# Sheet6.net
KiCad netlist of a schematic drawn in Altium Designer
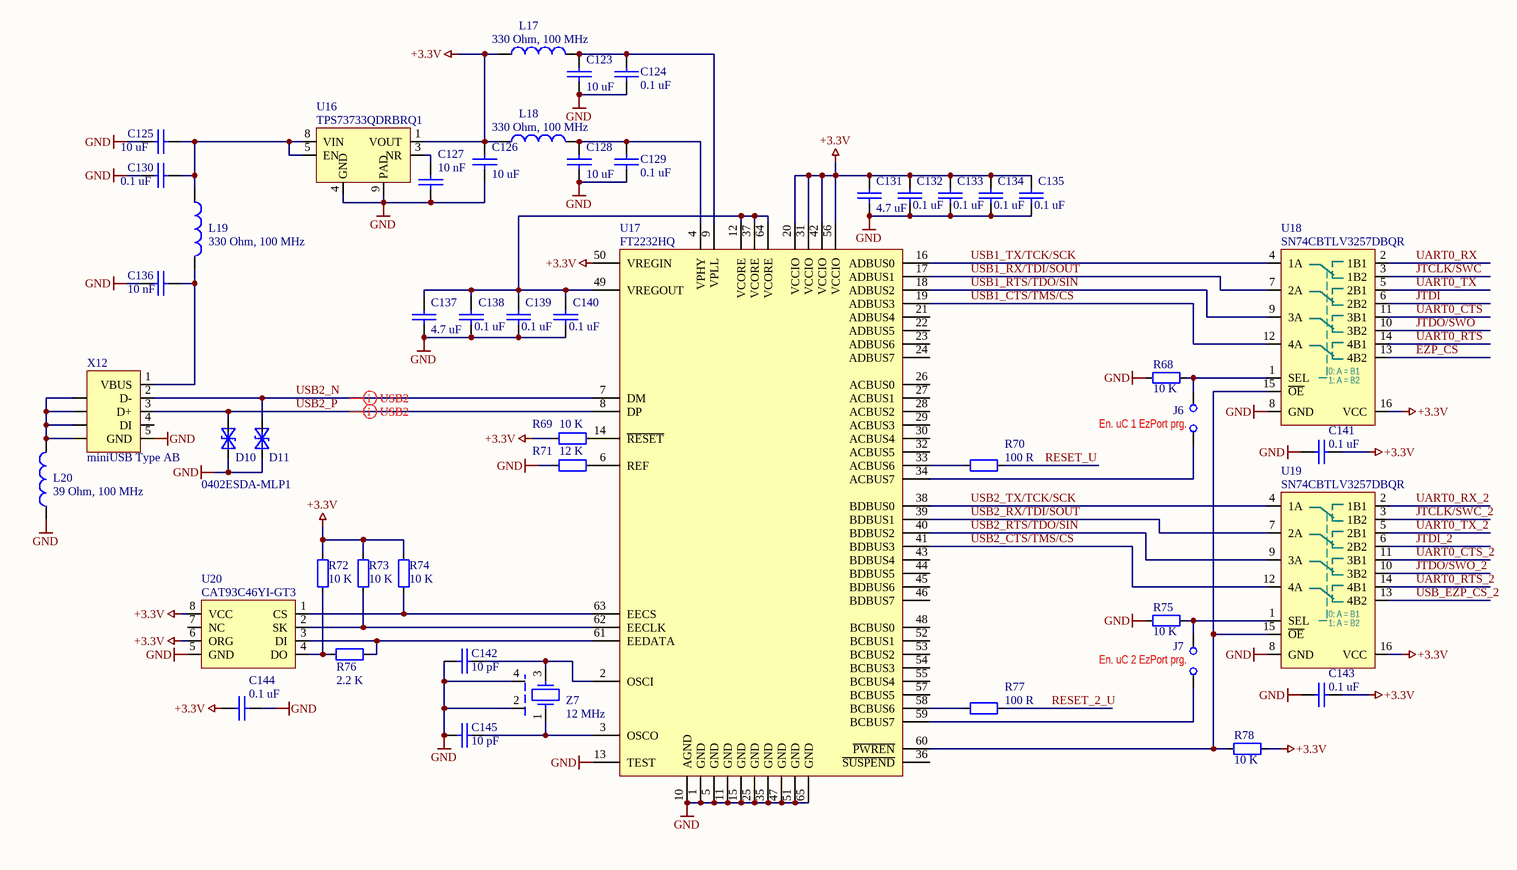
[diagram p0: Sheet6.SchDoc]

(export (version "E")
  (design (tool "Eeschema 10.0.6"))
  (components
    (comp (ref "C123")
      (value "10 uF")
      (footprint "2012[0805]")
      (description "10 uF, 16V, X5R, ±10%, 0805")
      (fields (field (name "MANUFACTURER") "TDK Corporation") (field (name "TOLERANCE") "±10%"))
      (libsource (lib "ea_Capacitors") (part "C2012X5R1C106K/0.85"))
    )
    (comp (ref "C124")
      (value "0.1 uF")
      (footprint "1005[0402]")
      (description "0.1 uF, 16V, 10%, X7R, 0402")
      (fields (field (name "TOLERANCE") "10%") (field (name "MANUFACTURER") "Murata"))
      (libsource (lib "ea_Capacitors") (part "GRM155R71C104KA88D"))
    )
    (comp (ref "C125")
      (value "10 uF")
      (footprint "2012[0805]")
      (description "10 uF, 16V, X5R, ±10%, 0805")
      (fields (field (name "MANUFACTURER") "TDK Corporation") (field (name "TOLERANCE") "±10%"))
      (libsource (lib "ea_Capacitors") (part "C2012X5R1C106K/0.85"))
    )
    (comp (ref "C126")
      (value "10 uF")
      (footprint "2012[0805]")
      (description "10 uF, 16V, X5R, ±10%, 0805")
      (fields (field (name "MANUFACTURER") "TDK Corporation") (field (name "TOLERANCE") "±10%"))
      (libsource (lib "ea_Capacitors") (part "C2012X5R1C106K/0.85"))
    )
    (comp (ref "C127")
      (value "10 nF")
      (footprint "1005[0402]")
      (description "10 nF, 16V, 10%, X7R, 0402")
      (fields (field (name "TOLERANCE") "10%") (field (name "MANUFACTURER") "SAMSUNG"))
      (libsource (lib "ea_Capacitors") (part "GRM155R71C103KA01D_1"))
    )
    (comp (ref "C128")
      (value "10 uF")
      (footprint "2012[0805]")
      (description "10 uF, 16V, X5R, ±10%, 0805")
      (fields (field (name "MANUFACTURER") "TDK Corporation") (field (name "TOLERANCE") "±10%"))
      (libsource (lib "ea_Capacitors") (part "C2012X5R1C106K/0.85"))
    )
    (comp (ref "C129")
      (value "0.1 uF")
      (footprint "1005[0402]")
      (description "0.1 uF, 16V, 10%, X7R, 0402")
      (fields (field (name "TOLERANCE") "10%") (field (name "MANUFACTURER") "Murata"))
      (libsource (lib "ea_Capacitors") (part "GRM155R71C104KA88D"))
    )
    (comp (ref "C130")
      (value "0.1 uF")
      (footprint "1608[0603]")
      (description "0.1 uF, 25V, 10% , X7R,  0603 SMD MLC Capacitor")
      (fields (field (name "TOLERANCE") "10%") (field (name "MANUFACTURER") "SAMSUNG"))
      (libsource (lib "ea_Capacitors") (part "CVNF100K0603-25"))
    )
    (comp (ref "C131")
      (value "4.7 uF")
      (footprint "1608[0603]")
      (description "4.7 uF, 10V, 10%, X5R, 0603")
      (fields (field (name "TOLERANCE") "+-10%") (field (name "MANUFACTURER") "Taiyo Yuden"))
      (libsource (lib "ea_Capacitors") (part "LMK107BJ475KA-T"))
    )
    (comp (ref "C132")
      (value "0.1 uF")
      (footprint "1005[0402]")
      (description "0.1 uF, 16V, 10%, X7R, 0402")
      (fields (field (name "TOLERANCE") "10%") (field (name "MANUFACTURER") "Murata"))
      (libsource (lib "ea_Capacitors") (part "GRM155R71C104KA88D"))
    )
    (comp (ref "C133")
      (value "0.1 uF")
      (footprint "1005[0402]")
      (description "0.1 uF, 16V, 10%, X7R, 0402")
      (fields (field (name "TOLERANCE") "10%") (field (name "MANUFACTURER") "Murata"))
      (libsource (lib "ea_Capacitors") (part "GRM155R71C104KA88D"))
    )
    (comp (ref "C134")
      (value "0.1 uF")
      (footprint "1005[0402]")
      (description "0.1 uF, 16V, 10%, X7R, 0402")
      (fields (field (name "TOLERANCE") "10%") (field (name "MANUFACTURER") "Murata"))
      (libsource (lib "ea_Capacitors") (part "GRM155R71C104KA88D"))
    )
    (comp (ref "C135")
      (value "0.1 uF")
      (footprint "1005[0402]")
      (description "0.1 uF, 16V, 10%, X7R, 0402")
      (fields (field (name "TOLERANCE") "10%") (field (name "MANUFACTURER") "Murata"))
      (libsource (lib "ea_Capacitors") (part "GRM155R71C104KA88D"))
    )
    (comp (ref "C136")
      (value "10 nF")
      (footprint "1608[0603]")
      (description "10 nF, 50V, 5%, X7R, 0603 SMD MLC Capacitor")
      (fields (field (name "TOLERANCE") "5%") (field (name "MANUFACTURER") "SAMSUNG"))
      (libsource (lib "ea_Capacitors") (part "CVNF010K0603"))
    )
    (comp (ref "C137")
      (value "4.7 uF")
      (footprint "1608[0603]")
      (description "4.7 uF, 10V, 10%, X5R, 0603")
      (fields (field (name "TOLERANCE") "+-10%") (field (name "MANUFACTURER") "Taiyo Yuden"))
      (libsource (lib "ea_Capacitors") (part "LMK107BJ475KA-T"))
    )
    (comp (ref "C138")
      (value "0.1 uF")
      (footprint "1005[0402]")
      (description "0.1 uF, 16V, 10%, X7R, 0402")
      (fields (field (name "TOLERANCE") "10%") (field (name "MANUFACTURER") "Murata"))
      (libsource (lib "ea_Capacitors") (part "GRM155R71C104KA88D"))
    )
    (comp (ref "C139")
      (value "0.1 uF")
      (footprint "1005[0402]")
      (description "0.1 uF, 16V, 10%, X7R, 0402")
      (fields (field (name "TOLERANCE") "10%") (field (name "MANUFACTURER") "Murata"))
      (libsource (lib "ea_Capacitors") (part "GRM155R71C104KA88D"))
    )
    (comp (ref "C140")
      (value "0.1 uF")
      (footprint "1005[0402]")
      (description "0.1 uF, 16V, 10%, X7R, 0402")
      (fields (field (name "TOLERANCE") "10%") (field (name "MANUFACTURER") "Murata"))
      (libsource (lib "ea_Capacitors") (part "GRM155R71C104KA88D"))
    )
    (comp (ref "C141")
      (value "0.1 uF")
      (footprint "1005[0402]")
      (description "0.1 uF, 16V, 10%, X7R, 0402")
      (fields (field (name "TOLERANCE") "10%") (field (name "MANUFACTURER") "Murata"))
      (libsource (lib "ea_Capacitors") (part "GRM155R71C104KA88D"))
    )
    (comp (ref "C142")
      (value "10 pF")
      (footprint "1608[0603]")
      (description "10 pF, 50V, 5%, NP0, 0603 SMD MLC Capacitor")
      (fields (field (name "MANUFACTURER") "Kemet") (field (name "TOLERANCE") "5%"))
      (libsource (lib "ea_Capacitors") (part "CCPF010K0603"))
    )
    (comp (ref "C143")
      (value "0.1 uF")
      (footprint "1005[0402]")
      (description "0.1 uF, 16V, 10%, X7R, 0402")
      (fields (field (name "TOLERANCE") "10%") (field (name "MANUFACTURER") "Murata"))
      (libsource (lib "ea_Capacitors") (part "GRM155R71C104KA88D"))
    )
    (comp (ref "C144")
      (value "0.1 uF")
      (footprint "1005[0402]")
      (description "0.1 uF, 16V, 10%, X7R, 0402")
      (fields (field (name "TOLERANCE") "10%") (field (name "MANUFACTURER") "Murata"))
      (libsource (lib "ea_Capacitors") (part "GRM155R71C104KA88D"))
    )
    (comp (ref "C145")
      (value "10 pF")
      (footprint "1608[0603]")
      (description "10 pF, 50V, 5%, NP0, 0603 SMD MLC Capacitor")
      (fields (field (name "MANUFACTURER") "Kemet") (field (name "TOLERANCE") "5%"))
      (libsource (lib "ea_Capacitors") (part "CCPF010K0603"))
    )
    (comp (ref "D10")
      (value "0402ESDA-MLP1")
      (footprint "0402")
      (description "SUPPRESSOR ESD 30VDC 0402 HFREE")
      (fields (field (name "MANUFACTURER") "Cooper Bussmann") (field (name "PARTNUM") "283-2964-2-ND"))
      (libsource (lib "ea_TVS_protection") (part "0402ESDA-MLP1"))
    )
    (comp (ref "D11")
      (value "0402ESDA-MLP1")
      (footprint "0402")
      (description "SUPPRESSOR ESD 30VDC 0402 HFREE")
      (fields (field (name "MANUFACTURER") "Cooper Bussmann") (field (name "PARTNUM") "283-2964-2-ND"))
      (libsource (lib "ea_TVS_protection") (part "0402ESDA-MLP1"))
    )
    (comp (ref "J6")
      (value "PH1-02-TA-HT")
      (footprint "HDR1X2V")
      (description "2 Pos. 2.54 mm Single Row Through Hole Straight Pin Header")
      (fields (field (name "MANUFACTURER") "ADAM TECH"))
      (libsource (lib "ea_Commutation") (part "Jumper"))
    )
    (comp (ref "J7")
      (value "PH1-02-TA-HT")
      (footprint "HDR1X2V")
      (description "2 Pos. 2.54 mm Single Row Through Hole Straight Pin Header")
      (fields (field (name "MANUFACTURER") "ADAM TECH"))
      (libsource (lib "ea_Commutation") (part "Jumper"))
    )
    (comp (ref "L17")
      (value "330 Ohm, 100 MHz")
      (footprint "0603")
      (description "Ferrite bead, 330 Ohm, 100 MHz,  1.5 A, 0.07 Ohm")
      (fields
        (field (name "MANUFACTURER") "Murata Electronics North America")
        (field (name "PARTNUM") "BLM18SG331TN1D")
      )
      (libsource (lib "*") (part "BLM18SG331TN1D"))
    )
    (comp (ref "L18")
      (value "330 Ohm, 100 MHz")
      (footprint "0603")
      (description "Ferrite bead, 330 Ohm, 100 MHz,  1.5 A, 0.07 Ohm")
      (fields
        (field (name "MANUFACTURER") "Murata Electronics North America")
        (field (name "PARTNUM") "BLM18SG331TN1D")
      )
      (libsource (lib "*") (part "BLM18SG331TN1D"))
    )
    (comp (ref "L19")
      (value "330 Ohm, 100 MHz")
      (footprint "0603")
      (description "Ferrite bead, 330 Ohm, 100 MHz,  1.5 A, 0.07 Ohm")
      (fields
        (field (name "MANUFACTURER") "Murata Electronics North America")
        (field (name "PARTNUM") "BLM18SG331TN1D")
      )
      (libsource (lib "*") (part "BLM18SG331TN1D"))
    )
    (comp (ref "L20")
      (value "39 Ohm, 100 MHz")
      (footprint "0805")
      (description "Ferrite bead, 39 Ohm, 100 MHz,  4 A")
      (fields (field (name "MANUFACTURER") "Panasonic - ECG") (field (name "PARTNUM") "P10191TR-ND"))
      (libsource (lib "*") (part "EXC-ML20A390U"))
    )
    (comp (ref "R68")
      (value "10 K")
      (footprint "0603")
      (description "10 K, 1%, 0603, SMD Resistor, Taped")
      (fields (field (name "MANUFACTURER") "PANASONIC") (field (name "TOLERANCE") "1%"))
      (libsource (lib "ea_Resistors") (part "RL0603K010-1"))
    )
    (comp (ref "R69")
      (value "10 K")
      (footprint "0603")
      (description "10 K, 1%, 0603, SMD Resistor, Taped")
      (fields (field (name "MANUFACTURER") "PANASONIC") (field (name "TOLERANCE") "1%"))
      (libsource (lib "") (part "RL0603K010-1_2"))
    )
    (comp (ref "R70")
      (value "100 R")
      (footprint "0603")
      (description "100 R, 1%, 0603, SMD Resistor, Taped")
      (fields (field (name "MANUFACTURER") "PANASONIC") (field (name "TOLERANCE") "1%"))
      (libsource (lib "ea_Resistors") (part "RL0603E100-1"))
    )
    (comp (ref "R71")
      (value "12 K")
      (footprint "0603")
      (description "12 K, 1%, 0603, SMD Resistor, Taped")
      (fields (field (name "MANUFACTURER") "YAGEO AMERICA CORPORATION") (field (name "TOLERANCE") "1%"))
      (libsource (lib "ea_Resistors") (part "RL0603K012-1_1"))
    )
    (comp (ref "R72")
      (value "10 K")
      (footprint "0603")
      (description "10 K, 1%, 0603, SMD Resistor, Taped")
      (fields (field (name "MANUFACTURER") "PANASONIC") (field (name "TOLERANCE") "1%"))
      (libsource (lib "") (part "RL0603K010-1_1"))
    )
    (comp (ref "R73")
      (value "10 K")
      (footprint "0603")
      (description "10 K, 1%, 0603, SMD Resistor, Taped")
      (fields (field (name "MANUFACTURER") "PANASONIC") (field (name "TOLERANCE") "1%"))
      (libsource (lib "") (part "RL0603K010-1_1"))
    )
    (comp (ref "R74")
      (value "10 K")
      (footprint "0603")
      (description "10 K, 1%, 0603, SMD Resistor, Taped")
      (fields (field (name "MANUFACTURER") "PANASONIC") (field (name "TOLERANCE") "1%"))
      (libsource (lib "") (part "RL0603K010-1_1"))
    )
    (comp (ref "R75")
      (value "10 K")
      (footprint "0603")
      (description "10 K, 1%, 0603, SMD Resistor, Taped")
      (fields (field (name "MANUFACTURER") "PANASONIC") (field (name "TOLERANCE") "1%"))
      (libsource (lib "ea_Resistors") (part "RL0603K010-1"))
    )
    (comp (ref "R76")
      (value "2.2 K")
      (footprint "0603")
      (description "2.2 K, 1%, 0603, SMD Resistor, Taped")
      (fields (field (name "MANUFACTURER") "YAGEO AMERICA CORPORATION") (field (name "TOLERANCE") "1%"))
      (libsource (lib "ea_Resistors") (part "RL0603K002.2-1_1"))
    )
    (comp (ref "R77")
      (value "100 R")
      (footprint "0603")
      (description "100 R, 1%, 0603, SMD Resistor, Taped")
      (fields (field (name "MANUFACTURER") "PANASONIC") (field (name "TOLERANCE") "1%"))
      (libsource (lib "ea_Resistors") (part "RL0603E100-1"))
    )
    (comp (ref "R78")
      (value "10 K")
      (footprint "0603")
      (description "10 K, 1%, 0603, SMD Resistor, Taped")
      (fields (field (name "MANUFACTURER") "PANASONIC") (field (name "TOLERANCE") "1%"))
      (libsource (lib "ea_Resistors") (part "RL0603K010-1"))
    )
    (comp (ref "U16")
      (value "TPS73733QDRBRQ1")
      (footprint "TI DRB (S-PVSON-N8)")
      (description "LDO 3.3V 1A , up to 5.5 V, -40..125C,  8-SON")
      (fields (field (name "MANUFACTURER") "Texas Instruments") (field (name "PARTNUM") "296-24157-1-ND"))
      (libsource (lib "ea_IC_Power_Reg_Ref_Sw") (part "TPS73733QDRBRQ1"))
    )
    (comp (ref "U17")
      (value "FT2232HQ")
      (footprint "QFN-64")
      (description "Dual High Speed USB to Multipurpose UART/FIFO")
      (fields
        (field (name "MANUFACTURER") "FTDI, Future Technology Devices International Ltd")
        (field (name "PARTNUM") "768-1024-1-ND")
      )
      (libsource (lib "ea_IC_Interfaces") (part "FT2232HQ"))
    )
    (comp (ref "U18")
      (value "SN74CBTLV3257DBQR")
      (footprint "TI DBQ 16pin (R-PDSO-G16)")
      (description "LV DUAL FET MUX/DEMUX, 2.3..3.6V,  -40..85 C, 16SSOP")
      (fields (field (name "MANUFACTURER") "Texas Instruments") (field (name "PARTNUM") "296-9135-1-ND"))
      (libsource (lib "ea_IC_Logic") (part "SN74CBTLV3257DBQR"))
    )
    (comp (ref "U19")
      (value "SN74CBTLV3257DBQR")
      (footprint "TI DBQ 16pin (R-PDSO-G16)")
      (description "LV DUAL FET MUX/DEMUX, 2.3..3.6V,  -40..85 C, 16SSOP")
      (fields (field (name "MANUFACTURER") "Texas Instruments") (field (name "PARTNUM") "296-9135-1-ND"))
      (libsource (lib "ea_IC_Logic") (part "SN74CBTLV3257DBQR"))
    )
    (comp (ref "U20")
      (value "CAT93C46YI-GT3")
      (footprint "TSSOP-8")
      (description "EEPROM 1KBIT 2MHZ 8TSSOP, -40..85 C")
      (fields
        (field (name "MANUFACTURER") "ON Semiconductor")
        (field (name "PARTNUM") "CAT93C46YI-GT3OSCT-ND")
      )
      (libsource (lib "ea_IC_NOR_NAND_FLASH") (part "CAT93C46YI-GT3"))
    )
    (comp (ref "X12")
      (value "miniUSB Type AB")
      (footprint "USB AB 56579-0576 Molex")
      (description "SMD USB - OTG, miniUSB Type AB")
      (fields
        (field (name "MANUFACTURER") "Molex/Waldom Electronics Corp")
        (field (name "PARTNUM") "WM17122CT-ND")
      )
      (libsource (lib "ea_Connectors") (part "USB AB 56579-0576"))
    )
    (comp (ref "Z7")
      (value "12 MHz")
      (footprint "DSX321G")
      (description "12 MHz, 8 pF, ±15ppm, -10...+75 С")
      (fields (field (name "MANUFACTURER") "NDK") (field (name "PARTNUM") "644-1047-1-ND"))
      (libsource (lib "ea_OSC_CLK_GEN") (part "NX3225SA-12.000MHZ-STD-CSR-1"))
    )
  )
  (nets
    (net (code "1") (name "+3.3V") (class "Default")
      (node (ref "C126") (pin "1") (pinfunction "1_1") (pintype "passive"))
      (node (ref "C131") (pin "2") (pinfunction "2_2") (pintype "passive"))
      (node (ref "C132") (pin "2") (pinfunction "2_2") (pintype "passive"))
      (node (ref "C133") (pin "2") (pinfunction "2_2") (pintype "passive"))
      (node (ref "C134") (pin "2") (pinfunction "2_2") (pintype "passive"))
      (node (ref "C135") (pin "2") (pinfunction "2_2") (pintype "passive"))
      (node (ref "C141") (pin "1") (pinfunction "1_1") (pintype "passive"))
      (node (ref "C143") (pin "1") (pinfunction "1_1") (pintype "passive"))
      (node (ref "C144") (pin "2") (pinfunction "2_2") (pintype "passive"))
      (node (ref "L17") (pin "1") (pinfunction "1_1") (pintype "passive"))
      (node (ref "L18") (pin "1") (pinfunction "1_1") (pintype "passive"))
      (node (ref "R69") (pin "2") (pinfunction "2_2") (pintype "passive"))
      (node (ref "R72") (pin "2") (pinfunction "2_2") (pintype "passive"))
      (node (ref "R73") (pin "2") (pinfunction "2_2") (pintype "passive"))
      (node (ref "R74") (pin "2") (pinfunction "2_2") (pintype "passive"))
      (node (ref "R78") (pin "2") (pinfunction "2_2") (pintype "passive"))
      (node (ref "U16") (pin "1") (pinfunction "VOUT_1") (pintype "passive"))
      (node (ref "U17") (pin "20") (pinfunction "VCCIO_20") (pintype "passive"))
      (node (ref "U17") (pin "31") (pinfunction "VCCIO_31") (pintype "passive"))
      (node (ref "U17") (pin "42") (pinfunction "VCCIO_42") (pintype "passive"))
      (node (ref "U17") (pin "50") (pinfunction "VREGIN_50") (pintype "passive"))
      (node (ref "U17") (pin "56") (pinfunction "VCCIO_56") (pintype "passive"))
      (node (ref "U18") (pin "16") (pinfunction "VCC_16") (pintype "passive"))
      (node (ref "U19") (pin "16") (pinfunction "VCC_16") (pintype "passive"))
      (node (ref "U20") (pin "6") (pinfunction "ORG_6") (pintype "passive"))
      (node (ref "U20") (pin "8") (pinfunction "VCC_8") (pintype "passive"))
    )
    (net (code "2") (name "/EZP_CS") (class "Default")
      (node (ref "U18") (pin "13") (pinfunction "4B2_13") (pintype "passive"))
    )
    (net (code "3") (name "/JTCLK{slash}SWC") (class "Default")
      (node (ref "U18") (pin "3") (pinfunction "1B2_3") (pintype "passive"))
    )
    (net (code "4") (name "/JTCLK{slash}SWC_2") (class "Default")
      (node (ref "U19") (pin "3") (pinfunction "1B2_3") (pintype "passive"))
    )
    (net (code "5") (name "/JTDI") (class "Default")
      (node (ref "U18") (pin "6") (pinfunction "2B2_6") (pintype "passive"))
    )
    (net (code "6") (name "/JTDI_2") (class "Default")
      (node (ref "U19") (pin "6") (pinfunction "2B2_6") (pintype "passive"))
    )
    (net (code "7") (name "/JTDO{slash}SWO") (class "Default")
      (node (ref "U18") (pin "10") (pinfunction "3B2_10") (pintype "passive"))
    )
    (net (code "8") (name "/JTDO{slash}SWO_2") (class "Default")
      (node (ref "U19") (pin "10") (pinfunction "3B2_10") (pintype "passive"))
    )
    (net (code "9") (name "/RESET_2_U") (class "Default")
      (node (ref "R77") (pin "1") (pinfunction "1_1") (pintype "passive"))
    )
    (net (code "10") (name "/RESET_U") (class "Default")
      (node (ref "R70") (pin "1") (pinfunction "1_1") (pintype "passive"))
    )
    (net (code "11") (name "/UART0_CTS") (class "Default")
      (node (ref "U18") (pin "11") (pinfunction "3B1_11") (pintype "passive"))
    )
    (net (code "12") (name "/UART0_CTS_2") (class "Default")
      (node (ref "U19") (pin "11") (pinfunction "3B1_11") (pintype "passive"))
    )
    (net (code "13") (name "/UART0_RTS") (class "Default")
      (node (ref "U18") (pin "14") (pinfunction "4B1_14") (pintype "passive"))
    )
    (net (code "14") (name "/UART0_RTS_2") (class "Default")
      (node (ref "U19") (pin "14") (pinfunction "4B1_14") (pintype "passive"))
    )
    (net (code "15") (name "/UART0_RX") (class "Default")
      (node (ref "U18") (pin "2") (pinfunction "1B1_2") (pintype "passive"))
    )
    (net (code "16") (name "/UART0_RX_2") (class "Default")
      (node (ref "U19") (pin "2") (pinfunction "1B1_2") (pintype "passive"))
    )
    (net (code "17") (name "/UART0_TX") (class "Default")
      (node (ref "U18") (pin "5") (pinfunction "2B1_5") (pintype "passive"))
    )
    (net (code "18") (name "/UART0_TX_2") (class "Default")
      (node (ref "U19") (pin "5") (pinfunction "2B1_5") (pintype "passive"))
    )
    (net (code "19") (name "/USB1_CTS{slash}TMS{slash}CS") (class "Default")
      (node (ref "U17") (pin "19") (pinfunction "ADBUS3_19") (pintype "passive"))
      (node (ref "U18") (pin "12") (pinfunction "4A_12") (pintype "passive"))
    )
    (net (code "20") (name "/USB1_RTS{slash}TDO{slash}SIN") (class "Default")
      (node (ref "U17") (pin "18") (pinfunction "ADBUS2_18") (pintype "passive"))
      (node (ref "U18") (pin "9") (pinfunction "3A_9") (pintype "passive"))
    )
    (net (code "21") (name "/USB1_RX{slash}TDI{slash}SOUT") (class "Default")
      (node (ref "U17") (pin "17") (pinfunction "ADBUS1_17") (pintype "passive"))
      (node (ref "U18") (pin "7") (pinfunction "2A_7") (pintype "passive"))
    )
    (net (code "22") (name "/USB1_TX{slash}TCK{slash}SCK") (class "Default")
      (node (ref "U17") (pin "16") (pinfunction "ADBUS0_16") (pintype "passive"))
      (node (ref "U18") (pin "4") (pinfunction "1A_4") (pintype "passive"))
    )
    (net (code "23") (name "/USB2_CTS{slash}TMS{slash}CS") (class "Default")
      (node (ref "U17") (pin "41") (pinfunction "BDBUS3_41") (pintype "passive"))
      (node (ref "U19") (pin "12") (pinfunction "4A_12") (pintype "passive"))
    )
    (net (code "24") (name "/USB2_N") (class "Default")
      (node (ref "D11") (pin "2") (pinfunction "A_2") (pintype "passive"))
      (node (ref "U17") (pin "7") (pinfunction "DM_7") (pintype "passive"))
      (node (ref "X12") (pin "2") (pinfunction "D-_2") (pintype "bidirectional"))
    )
    (net (code "25") (name "/USB2_P") (class "Default")
      (node (ref "D10") (pin "2") (pinfunction "A_2") (pintype "passive"))
      (node (ref "U17") (pin "8") (pinfunction "DP_8") (pintype "passive"))
      (node (ref "X12") (pin "3") (pinfunction "D+_3") (pintype "bidirectional"))
    )
    (net (code "26") (name "/USB2_RTS{slash}TDO{slash}SIN") (class "Default")
      (node (ref "U17") (pin "40") (pinfunction "BDBUS2_40") (pintype "passive"))
      (node (ref "U19") (pin "9") (pinfunction "3A_9") (pintype "passive"))
    )
    (net (code "27") (name "/USB2_RX{slash}TDI{slash}SOUT") (class "Default")
      (node (ref "U17") (pin "39") (pinfunction "BDBUS1_39") (pintype "passive"))
      (node (ref "U19") (pin "7") (pinfunction "2A_7") (pintype "passive"))
    )
    (net (code "28") (name "/USB2_TX{slash}TCK{slash}SCK") (class "Default")
      (node (ref "U17") (pin "38") (pinfunction "BDBUS0_38") (pintype "passive"))
      (node (ref "U19") (pin "4") (pinfunction "1A_4") (pintype "passive"))
    )
    (net (code "29") (name "/USB_EZP_CS_2") (class "Default")
      (node (ref "U19") (pin "13") (pinfunction "4B2_13") (pintype "passive"))
    )
    (net (code "30") (name "GND") (class "Default")
      (node (ref "C123") (pin "2") (pinfunction "2_2") (pintype "passive"))
      (node (ref "C124") (pin "1") (pinfunction "1_1") (pintype "passive"))
      (node (ref "C125") (pin "1") (pinfunction "1_1") (pintype "passive"))
      (node (ref "C126") (pin "2") (pinfunction "2_2") (pintype "passive"))
      (node (ref "C127") (pin "2") (pinfunction "2_2") (pintype "passive"))
      (node (ref "C128") (pin "2") (pinfunction "2_2") (pintype "passive"))
      (node (ref "C129") (pin "1") (pinfunction "1_1") (pintype "passive"))
      (node (ref "C130") (pin "2") (pinfunction "2_2") (pintype "passive"))
      (node (ref "C131") (pin "1") (pinfunction "1_1") (pintype "passive"))
      (node (ref "C132") (pin "1") (pinfunction "1_1") (pintype "passive"))
      (node (ref "C133") (pin "1") (pinfunction "1_1") (pintype "passive"))
      (node (ref "C134") (pin "1") (pinfunction "1_1") (pintype "passive"))
      (node (ref "C135") (pin "1") (pinfunction "1_1") (pintype "passive"))
      (node (ref "C136") (pin "2") (pinfunction "2_2") (pintype "passive"))
      (node (ref "C137") (pin "1") (pinfunction "1_1") (pintype "passive"))
      (node (ref "C138") (pin "1") (pinfunction "1_1") (pintype "passive"))
      (node (ref "C139") (pin "1") (pinfunction "1_1") (pintype "passive"))
      (node (ref "C140") (pin "1") (pinfunction "1_1") (pintype "passive"))
      (node (ref "C141") (pin "2") (pinfunction "2_2") (pintype "passive"))
      (node (ref "C142") (pin "2") (pinfunction "2_2") (pintype "passive"))
      (node (ref "C143") (pin "2") (pinfunction "2_2") (pintype "passive"))
      (node (ref "C144") (pin "1") (pinfunction "1_1") (pintype "passive"))
      (node (ref "C145") (pin "2") (pinfunction "2_2") (pintype "passive"))
      (node (ref "D10") (pin "1") (pinfunction "C_1") (pintype "passive"))
      (node (ref "D11") (pin "1") (pinfunction "C_1") (pintype "passive"))
      (node (ref "L20") (pin "1") (pinfunction "1_1") (pintype "passive"))
      (node (ref "R68") (pin "1") (pinfunction "1_1") (pintype "passive"))
      (node (ref "R71") (pin "1") (pinfunction "1_1") (pintype "passive"))
      (node (ref "R75") (pin "1") (pinfunction "1_1") (pintype "passive"))
      (node (ref "U16") (pin "4") (pinfunction "GND_4") (pintype "power_in"))
      (node (ref "U16") (pin "9") (pinfunction "PAD_9") (pintype "passive"))
      (node (ref "U17") (pin "1") (pinfunction "GND_1") (pintype "passive"))
      (node (ref "U17") (pin "10") (pinfunction "AGND_10") (pintype "passive"))
      (node (ref "U17") (pin "11") (pinfunction "GND_11") (pintype "passive"))
      (node (ref "U17") (pin "13") (pinfunction "TEST_13") (pintype "passive"))
      (node (ref "U17") (pin "15") (pinfunction "GND_15") (pintype "passive"))
      (node (ref "U17") (pin "25") (pinfunction "GND_25") (pintype "passive"))
      (node (ref "U17") (pin "35") (pinfunction "GND_35") (pintype "passive"))
      (node (ref "U17") (pin "47") (pinfunction "GND_47") (pintype "passive"))
      (node (ref "U17") (pin "5") (pinfunction "GND_5") (pintype "passive"))
      (node (ref "U17") (pin "51") (pinfunction "GND_51") (pintype "passive"))
      (node (ref "U17") (pin "65") (pinfunction "GND_65") (pintype "passive"))
      (node (ref "U18") (pin "8") (pinfunction "GND_8") (pintype "passive"))
      (node (ref "U19") (pin "8") (pinfunction "GND_8") (pintype "passive"))
      (node (ref "U20") (pin "5") (pinfunction "GND_5") (pintype "passive"))
      (node (ref "X12") (pin "5") (pinfunction "GND_5") (pintype "power_in"))
      (node (ref "Z7") (pin "2") (pinfunction "2_2") (pintype "passive"))
      (node (ref "Z7") (pin "4") (pinfunction "4_4") (pintype "passive"))
    )
    (net (code "31") (name "Net-(L20-Pad2)") (class "Default")
      (node (ref "L20") (pin "2") (pinfunction "2_2") (pintype "passive"))
      (node (ref "X12") (pin "S1") (pinfunction "SHLD_S1") (pintype "passive"))
      (node (ref "X12") (pin "S2") (pinfunction "SHLD_S2") (pintype "passive"))
      (node (ref "X12") (pin "S3") (pinfunction "SHLD_S3") (pintype "passive"))
      (node (ref "X12") (pin "S4") (pinfunction "SHLD_S4") (pintype "passive"))
    )
    (net (code "32") (name "Net-(U16-EN)") (class "Default")
      (node (ref "C125") (pin "2") (pinfunction "2_2") (pintype "passive"))
      (node (ref "C130") (pin "1") (pinfunction "1_1") (pintype "passive"))
      (node (ref "L19") (pin "1") (pinfunction "1_1") (pintype "passive"))
      (node (ref "U16") (pin "5") (pinfunction "EN_5") (pintype "power_in"))
      (node (ref "U16") (pin "8") (pinfunction "VIN_8") (pintype "power_in"))
    )
    (net (code "33") (name "Net-(U16-NR)") (class "Default")
      (node (ref "C127") (pin "1") (pinfunction "1_1") (pintype "passive"))
      (node (ref "U16") (pin "3") (pinfunction "NR_3") (pintype "passive"))
    )
    (net (code "34") (name "Net-(U17-ACBUS6)") (class "Default")
      (node (ref "R70") (pin "2") (pinfunction "2_2") (pintype "passive"))
      (node (ref "U17") (pin "33") (pinfunction "ACBUS6_33") (pintype "passive"))
    )
    (net (code "35") (name "Net-(U17-ACBUS7)") (class "Default")
      (node (ref "J6") (pin "2") (pinfunction "2_2") (pintype "passive"))
      (node (ref "U17") (pin "34") (pinfunction "ACBUS7_34") (pintype "passive"))
    )
    (net (code "36") (name "Net-(U17-BCBUS6)") (class "Default")
      (node (ref "R77") (pin "2") (pinfunction "2_2") (pintype "passive"))
      (node (ref "U17") (pin "58") (pinfunction "BCBUS6_58") (pintype "passive"))
    )
    (net (code "37") (name "Net-(U17-BCBUS7)") (class "Default")
      (node (ref "J7") (pin "2") (pinfunction "2_2") (pintype "passive"))
      (node (ref "U17") (pin "59") (pinfunction "BCBUS7_59") (pintype "passive"))
    )
    (net (code "38") (name "Net-(U17-EECLK)") (class "Default")
      (node (ref "R73") (pin "1") (pinfunction "1_1") (pintype "passive"))
      (node (ref "U17") (pin "62") (pinfunction "EECLK_62") (pintype "passive"))
      (node (ref "U20") (pin "2") (pinfunction "SK_2") (pintype "passive"))
    )
    (net (code "39") (name "Net-(U17-EECS)") (class "Default")
      (node (ref "R74") (pin "1") (pinfunction "1_1") (pintype "passive"))
      (node (ref "U17") (pin "63") (pinfunction "EECS_63") (pintype "passive"))
      (node (ref "U20") (pin "1") (pinfunction "CS_1") (pintype "passive"))
    )
    (net (code "40") (name "Net-(U17-EEDATA)") (class "Default")
      (node (ref "R76") (pin "1") (pinfunction "1_1") (pintype "passive"))
      (node (ref "U17") (pin "61") (pinfunction "EEDATA_61") (pintype "passive"))
      (node (ref "U20") (pin "3") (pinfunction "DI_3") (pintype "passive"))
    )
    (net (code "41") (name "Net-(U17-OSCI)") (class "Default")
      (node (ref "C142") (pin "1") (pinfunction "1_1") (pintype "passive"))
      (node (ref "U17") (pin "2") (pinfunction "OSCI_2") (pintype "passive"))
      (node (ref "Z7") (pin "3") (pinfunction "3_3") (pintype "passive"))
    )
    (net (code "42") (name "Net-(U17-OSCO)") (class "Default")
      (node (ref "C145") (pin "1") (pinfunction "1_1") (pintype "passive"))
      (node (ref "U17") (pin "3") (pinfunction "OSCO_3") (pintype "passive"))
      (node (ref "Z7") (pin "1") (pinfunction "1_1") (pintype "passive"))
    )
    (net (code "43") (name "Net-(U17-REF)") (class "Default")
      (node (ref "R71") (pin "2") (pinfunction "2_2") (pintype "passive"))
      (node (ref "U17") (pin "6") (pinfunction "REF_6") (pintype "passive"))
    )
    (net (code "44") (name "Net-(U17-VPHY)") (class "Default")
      (node (ref "C128") (pin "1") (pinfunction "1_1") (pintype "passive"))
      (node (ref "C129") (pin "2") (pinfunction "2_2") (pintype "passive"))
      (node (ref "L18") (pin "2") (pinfunction "2_2") (pintype "passive"))
      (node (ref "U17") (pin "4") (pinfunction "VPHY_4") (pintype "passive"))
    )
    (net (code "45") (name "Net-(U17-VPLL)") (class "Default")
      (node (ref "C123") (pin "1") (pinfunction "1_1") (pintype "passive"))
      (node (ref "C124") (pin "2") (pinfunction "2_2") (pintype "passive"))
      (node (ref "L17") (pin "2") (pinfunction "2_2") (pintype "passive"))
      (node (ref "U17") (pin "9") (pinfunction "VPLL_9") (pintype "passive"))
    )
    (net (code "46") (name "Net-(U17-VREGOUT)") (class "Default")
      (node (ref "C137") (pin "2") (pinfunction "2_2") (pintype "passive"))
      (node (ref "C138") (pin "2") (pinfunction "2_2") (pintype "passive"))
      (node (ref "C139") (pin "2") (pinfunction "2_2") (pintype "passive"))
      (node (ref "C140") (pin "2") (pinfunction "2_2") (pintype "passive"))
      (node (ref "U17") (pin "12") (pinfunction "VCORE_12") (pintype "passive"))
      (node (ref "U17") (pin "37") (pinfunction "VCORE_37") (pintype "passive"))
      (node (ref "U17") (pin "49") (pinfunction "VREGOUT_49") (pintype "passive"))
      (node (ref "U17") (pin "64") (pinfunction "VCORE_64") (pintype "passive"))
    )
    (net (code "47") (name "Net-(U17-~{PWREN})") (class "Default")
      (node (ref "R78") (pin "1") (pinfunction "1_1") (pintype "passive"))
      (node (ref "U17") (pin "60") (pinfunction "~{PWREN}_60") (pintype "passive"))
      (node (ref "U18") (pin "15") (pinfunction "~{OE}_15") (pintype "passive"))
      (node (ref "U19") (pin "15") (pinfunction "~{OE}_15") (pintype "passive"))
    )
    (net (code "48") (name "Net-(U17-~{RESET})") (class "Default")
      (node (ref "R69") (pin "1") (pinfunction "1_1") (pintype "passive"))
      (node (ref "U17") (pin "14") (pinfunction "~{RESET}_14") (pintype "passive"))
    )
    (net (code "49") (name "Net-(U18-SEL)") (class "Default")
      (node (ref "J6") (pin "1") (pinfunction "1_1") (pintype "passive"))
      (node (ref "R68") (pin "2") (pinfunction "2_2") (pintype "passive"))
      (node (ref "U18") (pin "1") (pinfunction "SEL_1") (pintype "passive"))
    )
    (net (code "50") (name "Net-(U19-SEL)") (class "Default")
      (node (ref "J7") (pin "1") (pinfunction "1_1") (pintype "passive"))
      (node (ref "R75") (pin "2") (pinfunction "2_2") (pintype "passive"))
      (node (ref "U19") (pin "1") (pinfunction "SEL_1") (pintype "passive"))
    )
    (net (code "51") (name "Net-(U20-DO)") (class "Default")
      (node (ref "R72") (pin "1") (pinfunction "1_1") (pintype "passive"))
      (node (ref "R76") (pin "2") (pinfunction "2_2") (pintype "passive"))
      (node (ref "U20") (pin "4") (pinfunction "DO_4") (pintype "passive"))
    )
    (net (code "52") (name "Net-(X12-VBUS)") (class "Default")
      (node (ref "C136") (pin "1") (pinfunction "1_1") (pintype "passive"))
      (node (ref "L19") (pin "2") (pinfunction "2_2") (pintype "passive"))
      (node (ref "X12") (pin "1") (pinfunction "VBUS_1") (pintype "power_in"))
    )
    (net (code "53") (name "unconnected-(U17-ACBUS0-Pad26)") (class "Default")
      (node (ref "U17") (pin "26") (pinfunction "ACBUS0_26") (pintype "passive"))
    )
    (net (code "54") (name "unconnected-(U17-ACBUS1-Pad27)") (class "Default")
      (node (ref "U17") (pin "27") (pinfunction "ACBUS1_27") (pintype "passive"))
    )
    (net (code "55") (name "unconnected-(U17-ACBUS2-Pad28)") (class "Default")
      (node (ref "U17") (pin "28") (pinfunction "ACBUS2_28") (pintype "passive"))
    )
    (net (code "56") (name "unconnected-(U17-ACBUS3-Pad29)") (class "Default")
      (node (ref "U17") (pin "29") (pinfunction "ACBUS3_29") (pintype "passive"))
    )
    (net (code "57") (name "unconnected-(U17-ACBUS4-Pad30)") (class "Default")
      (node (ref "U17") (pin "30") (pinfunction "ACBUS4_30") (pintype "passive"))
    )
    (net (code "58") (name "unconnected-(U17-ACBUS5-Pad32)") (class "Default")
      (node (ref "U17") (pin "32") (pinfunction "ACBUS5_32") (pintype "passive"))
    )
    (net (code "59") (name "unconnected-(U17-ADBUS4-Pad21)") (class "Default")
      (node (ref "U17") (pin "21") (pinfunction "ADBUS4_21") (pintype "passive"))
    )
    (net (code "60") (name "unconnected-(U17-ADBUS5-Pad22)") (class "Default")
      (node (ref "U17") (pin "22") (pinfunction "ADBUS5_22") (pintype "passive"))
    )
    (net (code "61") (name "unconnected-(U17-ADBUS6-Pad23)") (class "Default")
      (node (ref "U17") (pin "23") (pinfunction "ADBUS6_23") (pintype "passive"))
    )
    (net (code "62") (name "unconnected-(U17-ADBUS7-Pad24)") (class "Default")
      (node (ref "U17") (pin "24") (pinfunction "ADBUS7_24") (pintype "passive"))
    )
    (net (code "63") (name "unconnected-(U17-BCBUS0-Pad48)") (class "Default")
      (node (ref "U17") (pin "48") (pinfunction "BCBUS0_48") (pintype "passive"))
    )
    (net (code "64") (name "unconnected-(U17-BCBUS1-Pad52)") (class "Default")
      (node (ref "U17") (pin "52") (pinfunction "BCBUS1_52") (pintype "passive"))
    )
    (net (code "65") (name "unconnected-(U17-BCBUS2-Pad53)") (class "Default")
      (node (ref "U17") (pin "53") (pinfunction "BCBUS2_53") (pintype "passive"))
    )
    (net (code "66") (name "unconnected-(U17-BCBUS3-Pad54)") (class "Default")
      (node (ref "U17") (pin "54") (pinfunction "BCBUS3_54") (pintype "passive"))
    )
    (net (code "67") (name "unconnected-(U17-BCBUS4-Pad55)") (class "Default")
      (node (ref "U17") (pin "55") (pinfunction "BCBUS4_55") (pintype "passive"))
    )
    (net (code "68") (name "unconnected-(U17-BCBUS5-Pad57)") (class "Default")
      (node (ref "U17") (pin "57") (pinfunction "BCBUS5_57") (pintype "passive"))
    )
    (net (code "69") (name "unconnected-(U17-BDBUS4-Pad43)") (class "Default")
      (node (ref "U17") (pin "43") (pinfunction "BDBUS4_43") (pintype "passive"))
    )
    (net (code "70") (name "unconnected-(U17-BDBUS5-Pad44)") (class "Default")
      (node (ref "U17") (pin "44") (pinfunction "BDBUS5_44") (pintype "passive"))
    )
    (net (code "71") (name "unconnected-(U17-BDBUS6-Pad45)") (class "Default")
      (node (ref "U17") (pin "45") (pinfunction "BDBUS6_45") (pintype "passive"))
    )
    (net (code "72") (name "unconnected-(U17-BDBUS7-Pad46)") (class "Default")
      (node (ref "U17") (pin "46") (pinfunction "BDBUS7_46") (pintype "passive"))
    )
    (net (code "73") (name "unconnected-(U17-~{SUSPEND}-Pad36)") (class "Default")
      (node (ref "U17") (pin "36") (pinfunction "~{SUSPEND}_36") (pintype "passive"))
    )
    (net (code "74") (name "unconnected-(U20-NC-Pad7)") (class "Default")
      (node (ref "U20") (pin "7") (pinfunction "NC_7") (pintype "passive"))
    )
    (net (code "75") (name "unconnected-(X12-DI-Pad4)") (class "Default")
      (node (ref "X12") (pin "4") (pinfunction "DI_4") (pintype "bidirectional"))
    )
  )
)
